# dimmer.net
KiCad netlist of a schematic drawn in Altium Designer
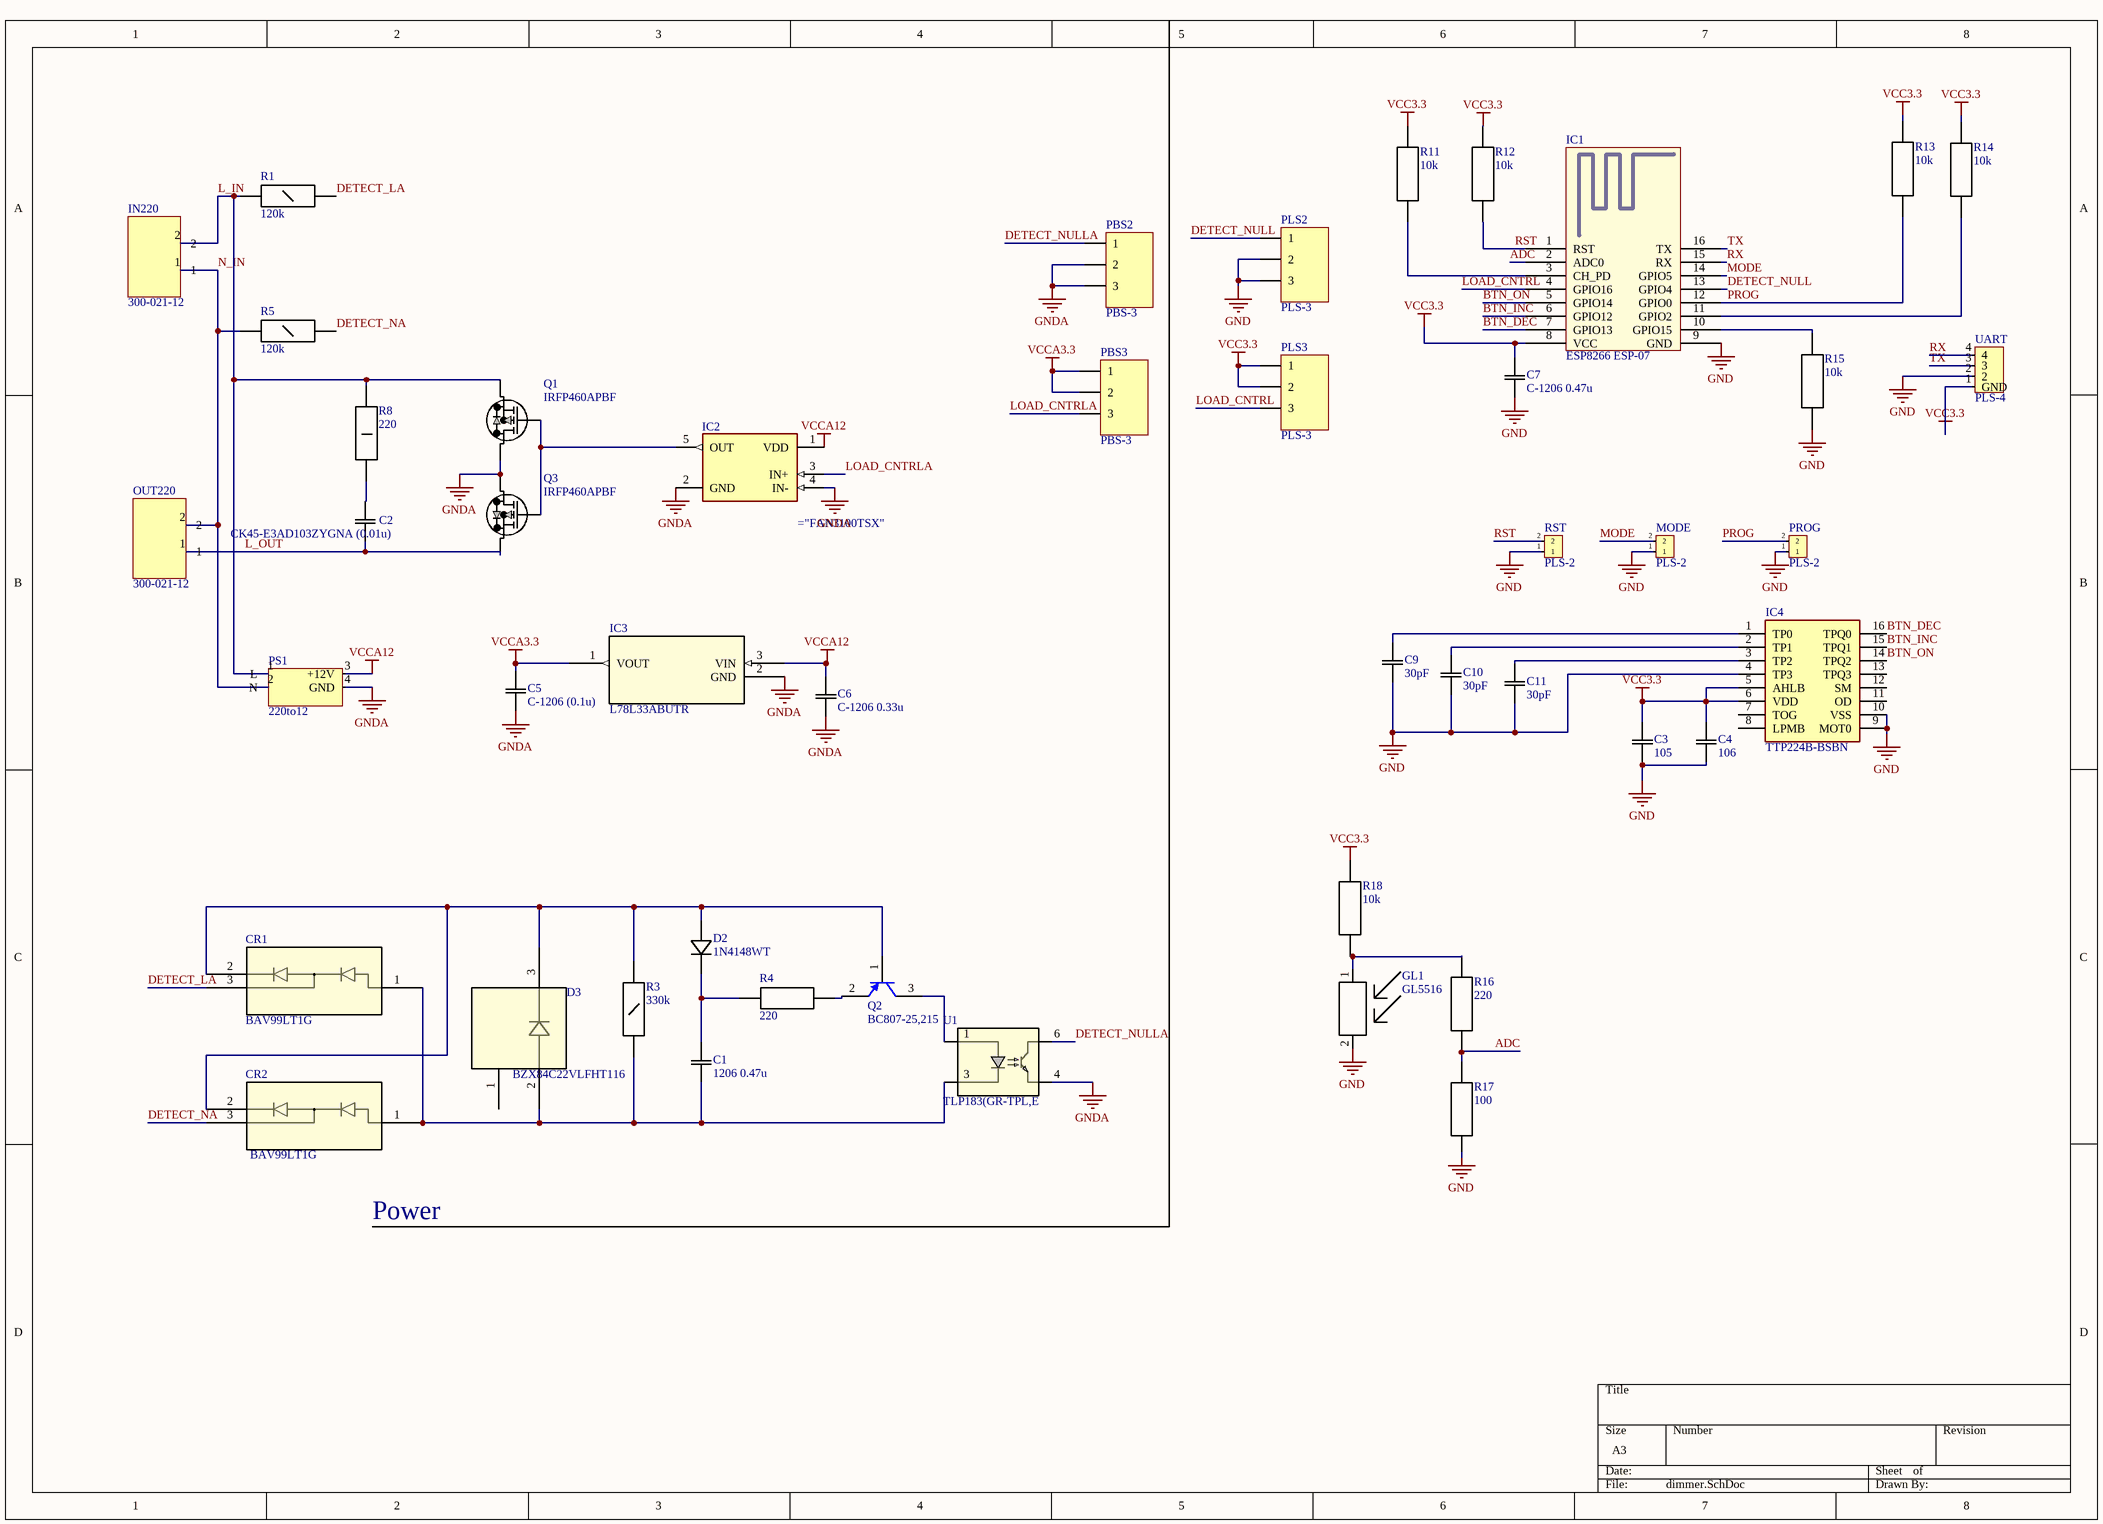
[diagram p0: dimmer.SchDoc]

(export (version "E")
  (design (tool "Eeschema 10.0.6"))
  (components
    (comp (ref "C1")
      (value "1206 0.47u")
      (footprint "CAP_X7R_1206_AVX")
      (description "No Description Available")
      (fields
        (field (name "MANUFACTURER_PART_NUMBER") "12061C104KAT2A")
        (field (name "COPYRIGHT") "Copyright (C) 2018 Accelerated Designs. All rights reserved")
      )
      (libsource (lib "diplom") (part "C-1206"))
    )
    (comp (ref "C2")
      (value "CK45-E3AD103ZYGNA (0.01u)")
      (footprint "CAP_CK45E3103_TDK")
      (description "No Description Available")
      (fields
        (field (name "MANUFACTURER_PART_NUMBER") "CK45-E3AD103ZYGNA")
        (field (name "COPYRIGHT") "Copyright (C) 2018 Accelerated Designs. All rights reserved")
      )
      (libsource (lib "diplom") (part "CK45-E3AD103ZYGNA"))
    )
    (comp (ref "C3")
      (value "105")
      (footprint "G-21_MUR")
      (description "cap0805")
      (fields
        (field (name "MANUFACTURER_PART_NUMBER") "GRM21BR71H224KA01L")
        (field (name "COPYRIGHT") "Copyright (C) 2015 Accelerated Designs. All rights reserved")
      )
      (libsource (lib "diplom") (part "cap0805"))
    )
    (comp (ref "C4")
      (value "106")
      (footprint "G-21_MUR")
      (description "cap0805")
      (fields
        (field (name "MANUFACTURER_PART_NUMBER") "GRM21BR71H224KA01L")
        (field (name "COPYRIGHT") "Copyright (C) 2015 Accelerated Designs. All rights reserved")
      )
      (libsource (lib "diplom") (part "cap0805"))
    )
    (comp (ref "C5")
      (value "C-1206 (0.1u)")
      (footprint "CAP_X7R_1206_AVX")
      (description "No Description Available")
      (fields
        (field (name "MANUFACTURER_PART_NUMBER") "12061C104KAT2A")
        (field (name "COPYRIGHT") "Copyright (C) 2018 Accelerated Designs. All rights reserved")
      )
      (libsource (lib "diplom") (part "C-1206"))
    )
    (comp (ref "C6")
      (value "C-1206 0.33u")
      (footprint "CAP_X7R_1206_AVX")
      (description "No Description Available")
      (fields
        (field (name "MANUFACTURER_PART_NUMBER") "12061C104KAT2A")
        (field (name "COPYRIGHT") "Copyright (C) 2018 Accelerated Designs. All rights reserved")
      )
      (libsource (lib "diplom") (part "C-1206"))
    )
    (comp (ref "C7")
      (value "C-1206 0.47u")
      (footprint "CAP_X7R_1206_AVX")
      (description "No Description Available")
      (fields
        (field (name "MANUFACTURER_PART_NUMBER") "12061C104KAT2A")
        (field (name "COPYRIGHT") "Copyright (C) 2018 Accelerated Designs. All rights reserved")
      )
      (libsource (lib "diplom") (part "C-1206"))
    )
    (comp (ref "C9")
      (value "30pF")
      (footprint "G-21_MUR")
      (description "cap0805")
      (fields
        (field (name "MANUFACTURER_PART_NUMBER") "GRM21BR71H224KA01L")
        (field (name "COPYRIGHT") "Copyright (C) 2015 Accelerated Designs. All rights reserved")
      )
      (libsource (lib "diplom") (part "cap0805"))
    )
    (comp (ref "C10")
      (value "30pF")
      (footprint "G-21_MUR")
      (description "cap0805")
      (fields
        (field (name "MANUFACTURER_PART_NUMBER") "GRM21BR71H224KA01L")
        (field (name "COPYRIGHT") "Copyright (C) 2015 Accelerated Designs. All rights reserved")
      )
      (libsource (lib "diplom") (part "cap0805"))
    )
    (comp (ref "C11")
      (value "30pF")
      (footprint "G-21_MUR")
      (description "cap0805")
      (fields
        (field (name "MANUFACTURER_PART_NUMBER") "GRM21BR71H224KA01L")
        (field (name "COPYRIGHT") "Copyright (C) 2015 Accelerated Designs. All rights reserved")
      )
      (libsource (lib "diplom") (part "cap0805"))
    )
    (comp (ref "CR1")
      (value "BAV99LT1G")
      (footprint "SOT-23_TO-236_318-08_ONS")
      (description "No Description Available")
      (fields (field (name "COPYRIGHT") "Copyright (C) 2018 Accelerated Designs. All rights reserved"))
      (libsource (lib "diplom") (part "BAV99LT1G"))
    )
    (comp (ref "CR2")
      (value "BAV99LT1G")
      (footprint "SOT-23_TO-236_318-08_ONS")
      (description "No Description Available")
      (fields (field (name "COPYRIGHT") "Copyright (C) 2018 Accelerated Designs. All rights reserved"))
      (libsource (lib "diplom") (part "BAV99LT1G"))
    )
    (comp (ref "D2")
      (value "1N4148WT")
      (footprint "CR_SOD-523F_ONS")
      (description "No Description Available")
      (fields (field (name "COPYRIGHT") "Copyright (C) 2018 Accelerated Designs. All rights reserved"))
      (libsource (lib "diplom") (part "1N4148WT"))
    )
    (comp (ref "D3")
      (value "BZX84C22VLFHT116")
      (footprint "TRANS_BZX84_ROM")
      (description "No Description Available")
      (fields (field (name "COPYRIGHT") "Copyright (C) 2018 Accelerated Designs. All rights reserved"))
      (libsource (lib "diplom") (part "BZX84C22VLFHT116"))
    )
    (comp (ref "GL1") (value "GL5516") (footprint "GL5516") (libsource (lib "diplom") (part "GL5516")))
    (comp (ref "IC1")
      (value "ESP8266 ESP-07")
      (footprint "ESP8266 ESP-07")
      (libsource (lib "diplom") (part "ESP8266 ESP-07"))
    )
    (comp (ref "IC2")
      (value "FAN3100TSX")
      (footprint "ON_Semi_527AH_0")
      (libsource (lib "diplom") (part "FAN3100TSX"))
    )
    (comp (ref "IC3")
      (value "L78L33ABUTR")
      (footprint "SOT-89_STM")
      (description "No Description Available")
      (fields (field (name "COPYRIGHT") "Copyright (C) 2018 Accelerated Designs. All rights reserved"))
      (libsource (lib "diplom") (part "L78L33ABUTR"))
    )
    (comp (ref "IC4")
      (value "TTP224B-BSBN")
      (footprint "SOP64P600X175-16N")
      (description "Integrated Circuit")
      (libsource (lib "diplom") (part "TTP224B-BSBN"))
    )
    (comp (ref "IN220")
      (value "300-021-12")
      (footprint "300-021-12")
      (libsource (lib "diplom") (part "300-021-12"))
    )
    (comp (ref "MODE") (value "PLS-2") (footprint "PLS-2") (libsource (lib "diplom") (part "PLS-2")))
    (comp (ref "OUT220")
      (value "300-021-12")
      (footprint "300-021-12")
      (libsource (lib "diplom") (part "300-021-12"))
    )
    (comp (ref "PBS2") (value "PBS-3") (footprint "PBS-3") (libsource (lib "diplom") (part "PBS-3")))
    (comp (ref "PBS3") (value "PBS-3") (footprint "PBS-3") (libsource (lib "diplom") (part "PBS-3")))
    (comp (ref "PLS2") (value "PLS-3") (footprint "PLS-3") (libsource (lib "diplom") (part "PLS-3")))
    (comp (ref "PLS3") (value "PLS-3") (footprint "PLS-3") (libsource (lib "diplom") (part "PLS-3")))
    (comp (ref "PROG") (value "PLS-2") (footprint "PLS-2") (libsource (lib "diplom") (part "PLS-2")))
    (comp (ref "PS1") (value "220to12") (footprint "220to12") (libsource (lib "diplom") (part "220to12")))
    (comp (ref "Q1")
      (value "IRFP460APBF")
      (footprint "TO-247AC_VIS")
      (description "No Description Available")
      (fields (field (name "COPYRIGHT") "Copyright (C) 2018 Accelerated Designs. All rights reserved"))
      (libsource (lib "diplom") (part "IRFP460APBF"))
    )
    (comp (ref "Q2")
      (value "BC807-25,215")
      (footprint "SOT23_BC807_NEX")
      (description "No Description Available")
      (fields (field (name "COPYRIGHT") "Copyright (C) 2016 Accelerated Designs. All rights reserved"))
      (libsource (lib "diplom") (part "BC807-25,215"))
    )
    (comp (ref "Q3")
      (value "IRFP460APBF")
      (footprint "TO-247AC_VIS")
      (description "No Description Available")
      (fields (field (name "COPYRIGHT") "Copyright (C) 2018 Accelerated Designs. All rights reserved"))
      (libsource (lib "diplom") (part "IRFP460APBF"))
    )
    (comp (ref "R1")
      (value "120k")
      (footprint "CAP_X7R_1206_AVX")
      (description "R-1206")
      (libsource (lib "diplom") (part "R-1206"))
    )
    (comp (ref "R3")
      (value "330k")
      (footprint "CAP_X7R_1206_AVX")
      (description "R-1206")
      (libsource (lib "diplom") (part "R-1206"))
    )
    (comp (ref "R4")
      (value "220")
      (footprint "G-21_MUR")
      (description "Resistor 0805")
      (libsource (lib "diplom") (part "res0805"))
    )
    (comp (ref "R5")
      (value "120k")
      (footprint "CAP_X7R_1206_AVX")
      (description "R-1206")
      (libsource (lib "diplom") (part "R-1206"))
    )
    (comp (ref "R8")
      (value "220")
      (footprint "RES2512_TL_TYCO_TYC")
      (description "No Description Available")
      (fields
        (field (name "MANUFACTURER_PART_NUMBER") "TL3AR033F")
        (field (name "COPYRIGHT") "Copyright (C) 2018 Accelerated Designs. All rights reserved")
      )
      (libsource (lib "diplom") (part "R-2512"))
    )
    (comp (ref "R11")
      (value "10k")
      (footprint "G-21_MUR")
      (description "Resistor 0805")
      (libsource (lib "diplom") (part "res0805"))
    )
    (comp (ref "R12")
      (value "10k")
      (footprint "G-21_MUR")
      (description "Resistor 0805")
      (libsource (lib "diplom") (part "res0805"))
    )
    (comp (ref "R13")
      (value "10k")
      (footprint "G-21_MUR")
      (description "Resistor 0805")
      (libsource (lib "diplom") (part "res0805"))
    )
    (comp (ref "R14")
      (value "10k")
      (footprint "G-21_MUR")
      (description "Resistor 0805")
      (libsource (lib "diplom") (part "res0805"))
    )
    (comp (ref "R15")
      (value "10k")
      (footprint "G-21_MUR")
      (description "Resistor 0805")
      (libsource (lib "diplom") (part "res0805"))
    )
    (comp (ref "R16")
      (value "220")
      (footprint "G-21_MUR")
      (description "Resistor 0805")
      (libsource (lib "diplom") (part "res0805"))
    )
    (comp (ref "R17")
      (value "100")
      (footprint "G-21_MUR")
      (description "Resistor 0805")
      (libsource (lib "diplom") (part "res0805"))
    )
    (comp (ref "R18")
      (value "10k")
      (footprint "G-21_MUR")
      (description "Resistor 0805")
      (libsource (lib "diplom") (part "res0805"))
    )
    (comp (ref "RST") (value "PLS-2") (footprint "PLS-2") (libsource (lib "diplom") (part "PLS-2")))
    (comp (ref "U1")
      (value "TLP183(GR-TPL,E")
      (footprint "4pin SO6_TOS")
      (description "No Description Available")
      (fields (field (name "COPYRIGHT") "Copyright (C) 2018 Accelerated Designs. All rights reserved"))
      (libsource (lib "diplom") (part "TLP183(GR-TPL,E"))
    )
    (comp (ref "UART") (value "PLS-4") (footprint "PLS-4") (libsource (lib "diplom") (part "PLS-4")))
  )
  (nets
    (net (code "1") (name "/ADC") (class "Default")
      (node (ref "IC1") (pin "2") (pinfunction "ADC0_2") (pintype "passive"))
      (node (ref "R16") (pin "1") (pinfunction "1_1") (pintype "passive"))
      (node (ref "R17") (pin "2") (pinfunction "2_2") (pintype "passive"))
    )
    (net (code "2") (name "/BTN_DEC") (class "Default")
      (node (ref "IC1") (pin "7") (pinfunction "GPIO13_7") (pintype "passive"))
      (node (ref "IC4") (pin "16") (pinfunction "TPQ0_16") (pintype "passive"))
    )
    (net (code "3") (name "/BTN_INC") (class "Default")
      (node (ref "IC1") (pin "6") (pinfunction "GPIO12_6") (pintype "passive"))
      (node (ref "IC4") (pin "15") (pinfunction "TPQ1_15") (pintype "passive"))
    )
    (net (code "4") (name "/BTN_ON") (class "Default")
      (node (ref "IC1") (pin "5") (pinfunction "GPIO14_5") (pintype "passive"))
      (node (ref "IC4") (pin "14") (pinfunction "TPQ2_14") (pintype "passive"))
    )
    (net (code "5") (name "/DETECT_LA") (class "Default")
      (node (ref "CR1") (pin "3") (pinfunction "3_3") (pintype "passive"))
      (node (ref "R1") (pin "2") (pinfunction "2_2") (pintype "passive"))
    )
    (net (code "6") (name "/DETECT_NA") (class "Default")
      (node (ref "CR2") (pin "3") (pinfunction "3_3") (pintype "passive"))
      (node (ref "R5") (pin "2") (pinfunction "2_2") (pintype "passive"))
    )
    (net (code "7") (name "/DETECT_NULL") (class "Default")
      (node (ref "IC1") (pin "13") (pinfunction "GPIO4_13") (pintype "passive"))
      (node (ref "PLS2") (pin "1") (pinfunction "1_1") (pintype "passive"))
    )
    (net (code "8") (name "/DETECT_NULLA") (class "Default")
      (node (ref "PBS2") (pin "1") (pinfunction "1_1") (pintype "passive"))
      (node (ref "U1") (pin "6") (pinfunction "6_6") (pintype "passive"))
    )
    (net (code "9") (name "/LOAD_CNTRL") (class "Default")
      (node (ref "IC1") (pin "4") (pinfunction "GPIO16_4") (pintype "passive"))
      (node (ref "PLS3") (pin "3") (pinfunction "3_3") (pintype "passive"))
    )
    (net (code "10") (name "/LOAD_CNTRLA") (class "Default")
      (node (ref "IC2") (pin "3") (pinfunction "IN+_3") (pintype "input"))
      (node (ref "PBS3") (pin "3") (pinfunction "3_3") (pintype "passive"))
    )
    (net (code "11") (name "/L_IN") (class "Default")
      (node (ref "IN220") (pin "2") (pinfunction "2_2") (pintype "passive"))
      (node (ref "PS1") (pin "1") (pinfunction "L_1") (pintype "passive"))
      (node (ref "Q1") (pin "3") (pinfunction "S_3") (pintype "passive"))
      (node (ref "R1") (pin "1") (pinfunction "1_1") (pintype "passive"))
      (node (ref "R8") (pin "2") (pinfunction "2_2") (pintype "passive"))
    )
    (net (code "12") (name "/L_OUT") (class "Default")
      (node (ref "C2") (pin "1") (pinfunction "1_1") (pintype "passive"))
      (node (ref "OUT220") (pin "1") (pinfunction "1_1") (pintype "passive"))
      (node (ref "Q3") (pin "3") (pinfunction "S_3") (pintype "passive"))
    )
    (net (code "13") (name "/MODE") (class "Default")
      (node (ref "IC1") (pin "14") (pinfunction "GPIO5_14") (pintype "passive"))
      (node (ref "MODE") (pin "2") (pinfunction "2_2") (pintype "passive"))
    )
    (net (code "14") (name "/N_IN") (class "Default")
      (node (ref "IN220") (pin "1") (pinfunction "1_1") (pintype "passive"))
      (node (ref "OUT220") (pin "2") (pinfunction "2_2") (pintype "passive"))
      (node (ref "PS1") (pin "2") (pinfunction "N_2") (pintype "passive"))
      (node (ref "R5") (pin "1") (pinfunction "1_1") (pintype "passive"))
    )
    (net (code "15") (name "/PROG") (class "Default")
      (node (ref "IC1") (pin "12") (pinfunction "GPIO0_12") (pintype "passive"))
      (node (ref "PROG") (pin "2") (pinfunction "2_2") (pintype "passive"))
      (node (ref "R13") (pin "1") (pinfunction "1_1") (pintype "passive"))
    )
    (net (code "16") (name "/RST") (class "Default")
      (node (ref "IC1") (pin "1") (pinfunction "RST_1") (pintype "power_in"))
      (node (ref "R12") (pin "1") (pinfunction "1_1") (pintype "passive"))
      (node (ref "RST") (pin "2") (pinfunction "2_2") (pintype "passive"))
    )
    (net (code "17") (name "/RX") (class "Default")
      (node (ref "IC1") (pin "15") (pinfunction "RX_15") (pintype "passive"))
      (node (ref "UART") (pin "4") (pinfunction "4_4") (pintype "passive"))
    )
    (net (code "18") (name "/TX") (class "Default")
      (node (ref "IC1") (pin "16") (pinfunction "TX_16") (pintype "passive"))
      (node (ref "UART") (pin "3") (pinfunction "3_3") (pintype "passive"))
    )
    (net (code "19") (name "GND") (class "Default")
      (node (ref "C10") (pin "1") (pinfunction "1_1") (pintype "passive"))
      (node (ref "C11") (pin "1") (pinfunction "1_1") (pintype "passive"))
      (node (ref "C3") (pin "1") (pinfunction "1_1") (pintype "passive"))
      (node (ref "C4") (pin "1") (pinfunction "1_1") (pintype "passive"))
      (node (ref "C7") (pin "1") (pinfunction "1_1") (pintype "passive"))
      (node (ref "C9") (pin "1") (pinfunction "1_1") (pintype "passive"))
      (node (ref "GL1") (pin "2") (pinfunction "2_2") (pintype "passive"))
      (node (ref "IC1") (pin "9") (pinfunction "GND_9") (pintype "passive"))
      (node (ref "IC4") (pin "10") (pinfunction "VSS_10") (pintype "passive"))
      (node (ref "IC4") (pin "4") (pinfunction "TP3_4") (pintype "passive"))
      (node (ref "IC4") (pin "9") (pinfunction "MOT0_9") (pintype "passive"))
      (node (ref "MODE") (pin "1") (pinfunction "1_1") (pintype "passive"))
      (node (ref "PLS2") (pin "2") (pinfunction "2_2") (pintype "passive"))
      (node (ref "PLS2") (pin "3") (pinfunction "3_3") (pintype "passive"))
      (node (ref "PROG") (pin "1") (pinfunction "1_1") (pintype "passive"))
      (node (ref "R15") (pin "1") (pinfunction "1_1") (pintype "passive"))
      (node (ref "R17") (pin "1") (pinfunction "1_1") (pintype "passive"))
      (node (ref "RST") (pin "1") (pinfunction "1_1") (pintype "passive"))
      (node (ref "UART") (pin "2") (pinfunction "2_2") (pintype "passive"))
    )
    (net (code "20") (name "GNDA") (class "Default")
      (node (ref "C5") (pin "1") (pinfunction "1_1") (pintype "passive"))
      (node (ref "C6") (pin "1") (pinfunction "1_1") (pintype "passive"))
      (node (ref "IC2") (pin "2") (pinfunction "GND_2") (pintype "power_in"))
      (node (ref "IC2") (pin "4") (pinfunction "IN-_4") (pintype "input"))
      (node (ref "IC3") (pin "2") (pinfunction "GND_2") (pintype "passive"))
      (node (ref "PBS2") (pin "2") (pinfunction "2_2") (pintype "passive"))
      (node (ref "PBS2") (pin "3") (pinfunction "3_3") (pintype "passive"))
      (node (ref "PS1") (pin "4") (pinfunction "GND_4") (pintype "passive"))
      (node (ref "Q1") (pin "2") (pinfunction "D_2") (pintype "passive"))
      (node (ref "Q3") (pin "2") (pinfunction "D_2") (pintype "passive"))
      (node (ref "U1") (pin "4") (pinfunction "4_4") (pintype "passive"))
    )
    (net (code "21") (name "Net-(C1-Pad2)") (class "Default")
      (node (ref "C1") (pin "2") (pinfunction "2_2") (pintype "passive"))
      (node (ref "D2") (pin "1") (pinfunction "1_1") (pintype "passive"))
      (node (ref "R4") (pin "1") (pinfunction "1_1") (pintype "passive"))
    )
    (net (code "22") (name "Net-(C2-Pad2)") (class "Default")
      (node (ref "C2") (pin "2") (pinfunction "2_2") (pintype "passive"))
      (node (ref "R8") (pin "1") (pinfunction "1_1") (pintype "passive"))
    )
    (net (code "23") (name "Net-(D3-1)") (class "Default")
      (node (ref "C1") (pin "1") (pinfunction "1_1") (pintype "passive"))
      (node (ref "CR1") (pin "1") (pinfunction "1_1") (pintype "passive"))
      (node (ref "CR2") (pin "1") (pinfunction "1_1") (pintype "passive"))
      (node (ref "D3") (pin "2") (pinfunction "1_2") (pintype "passive"))
      (node (ref "R3") (pin "1") (pinfunction "1_1") (pintype "passive"))
      (node (ref "U1") (pin "3") (pinfunction "3_3") (pintype "passive"))
    )
    (net (code "24") (name "Net-(GL1-Pad1)") (class "Default")
      (node (ref "GL1") (pin "1") (pinfunction "1_1") (pintype "passive"))
      (node (ref "R16") (pin "2") (pinfunction "2_2") (pintype "passive"))
      (node (ref "R18") (pin "1") (pinfunction "1_1") (pintype "passive"))
    )
    (net (code "25") (name "Net-(IC1-CH_PD)") (class "Default")
      (node (ref "IC1") (pin "3") (pinfunction "CH_PD_3") (pintype "passive"))
      (node (ref "R11") (pin "1") (pinfunction "1_1") (pintype "passive"))
    )
    (net (code "26") (name "Net-(IC1-GPIO2)") (class "Default")
      (node (ref "IC1") (pin "11") (pinfunction "GPIO2_11") (pintype "passive"))
      (node (ref "R14") (pin "1") (pinfunction "1_1") (pintype "passive"))
    )
    (net (code "27") (name "Net-(IC1-GPIO15)") (class "Default")
      (node (ref "IC1") (pin "10") (pinfunction "GPIO15_10") (pintype "passive"))
      (node (ref "R15") (pin "2") (pinfunction "2_2") (pintype "passive"))
    )
    (net (code "28") (name "Net-(IC2-OUT)") (class "Default")
      (node (ref "IC2") (pin "5") (pinfunction "OUT_5") (pintype "output"))
      (node (ref "Q1") (pin "1") (pinfunction "G_1") (pintype "passive"))
      (node (ref "Q3") (pin "1") (pinfunction "G_1") (pintype "passive"))
    )
    (net (code "29") (name "Net-(IC4-TP0)") (class "Default")
      (node (ref "C9") (pin "2") (pinfunction "2_2") (pintype "passive"))
      (node (ref "IC4") (pin "1") (pinfunction "TP0_1") (pintype "passive"))
    )
    (net (code "30") (name "Net-(IC4-TP1)") (class "Default")
      (node (ref "C10") (pin "2") (pinfunction "2_2") (pintype "passive"))
      (node (ref "IC4") (pin "2") (pinfunction "TP1_2") (pintype "passive"))
    )
    (net (code "31") (name "Net-(IC4-TP2)") (class "Default")
      (node (ref "C11") (pin "2") (pinfunction "2_2") (pintype "passive"))
      (node (ref "IC4") (pin "3") (pinfunction "TP2_3") (pintype "passive"))
    )
    (net (code "32") (name "Net-(Q2-B)") (class "Default")
      (node (ref "CR1") (pin "2") (pinfunction "2_2") (pintype "passive"))
      (node (ref "CR2") (pin "2") (pinfunction "2_2") (pintype "passive"))
      (node (ref "D2") (pin "2") (pinfunction "2_2") (pintype "passive"))
      (node (ref "D3") (pin "3") (pinfunction "3_3") (pintype "passive"))
      (node (ref "Q2") (pin "1") (pinfunction "B_1") (pintype "passive"))
      (node (ref "R3") (pin "2") (pinfunction "2_2") (pintype "passive"))
    )
    (net (code "33") (name "Net-(Q2-C)") (class "Default")
      (node (ref "Q2") (pin "3") (pinfunction "C_3") (pintype "passive"))
      (node (ref "U1") (pin "1") (pinfunction "1_1") (pintype "passive"))
    )
    (net (code "34") (name "Net-(Q2-Pad2)") (class "Default")
      (node (ref "Q2") (pin "2") (pintype "passive"))
      (node (ref "R4") (pin "2") (pinfunction "2_2") (pintype "passive"))
    )
    (net (code "35") (name "VCC3.3") (class "Default")
      (node (ref "C3") (pin "2") (pinfunction "2_2") (pintype "passive"))
      (node (ref "C4") (pin "2") (pinfunction "2_2") (pintype "passive"))
      (node (ref "C7") (pin "2") (pinfunction "2_2") (pintype "passive"))
      (node (ref "IC1") (pin "8") (pinfunction "VCC_8") (pintype "passive"))
      (node (ref "IC4") (pin "5") (pinfunction "AHLB_5") (pintype "passive"))
      (node (ref "IC4") (pin "6") (pinfunction "VDD_6") (pintype "passive"))
      (node (ref "PLS3") (pin "1") (pinfunction "1_1") (pintype "passive"))
      (node (ref "PLS3") (pin "2") (pinfunction "2_2") (pintype "passive"))
      (node (ref "R11") (pin "2") (pinfunction "2_2") (pintype "passive"))
      (node (ref "R12") (pin "2") (pinfunction "2_2") (pintype "passive"))
      (node (ref "R13") (pin "2") (pinfunction "2_2") (pintype "passive"))
      (node (ref "R14") (pin "2") (pinfunction "2_2") (pintype "passive"))
      (node (ref "R18") (pin "2") (pinfunction "2_2") (pintype "passive"))
      (node (ref "UART") (pin "1") (pinfunction "GND_1") (pintype "passive"))
    )
    (net (code "36") (name "VCCA3.3") (class "Default")
      (node (ref "C5") (pin "2") (pinfunction "2_2") (pintype "passive"))
      (node (ref "IC3") (pin "1") (pinfunction "VOUT_1") (pintype "output"))
      (node (ref "PBS3") (pin "1") (pinfunction "1_1") (pintype "passive"))
      (node (ref "PBS3") (pin "2") (pinfunction "2_2") (pintype "passive"))
    )
    (net (code "37") (name "VCCA12") (class "Default")
      (node (ref "C6") (pin "2") (pinfunction "2_2") (pintype "passive"))
      (node (ref "IC2") (pin "1") (pinfunction "VDD_1") (pintype "power_in"))
      (node (ref "IC3") (pin "3") (pinfunction "VIN_3") (pintype "input"))
      (node (ref "PS1") (pin "3") (pinfunction "+12V_3") (pintype "passive"))
    )
    (net (code "38") (name "unconnected-(D3-2-Pad1)") (class "Default")
      (node (ref "D3") (pin "1") (pinfunction "2_1") (pintype "passive"))
    )
    (net (code "39") (name "unconnected-(IC4-LPMB-Pad8)") (class "Default")
      (node (ref "IC4") (pin "8") (pinfunction "LPMB_8") (pintype "passive"))
    )
    (net (code "40") (name "unconnected-(IC4-OD-Pad11)") (class "Default")
      (node (ref "IC4") (pin "11") (pinfunction "OD_11") (pintype "passive"))
    )
    (net (code "41") (name "unconnected-(IC4-SM-Pad12)") (class "Default")
      (node (ref "IC4") (pin "12") (pinfunction "SM_12") (pintype "passive"))
    )
    (net (code "42") (name "unconnected-(IC4-TOG-Pad7)") (class "Default")
      (node (ref "IC4") (pin "7") (pinfunction "TOG_7") (pintype "passive"))
    )
    (net (code "43") (name "unconnected-(IC4-TPQ3-Pad13)") (class "Default")
      (node (ref "IC4") (pin "13") (pinfunction "TPQ3_13") (pintype "passive"))
    )
  )
)
